# MB_RELAY.net
KiCad netlist of a schematic drawn in Altium Designer
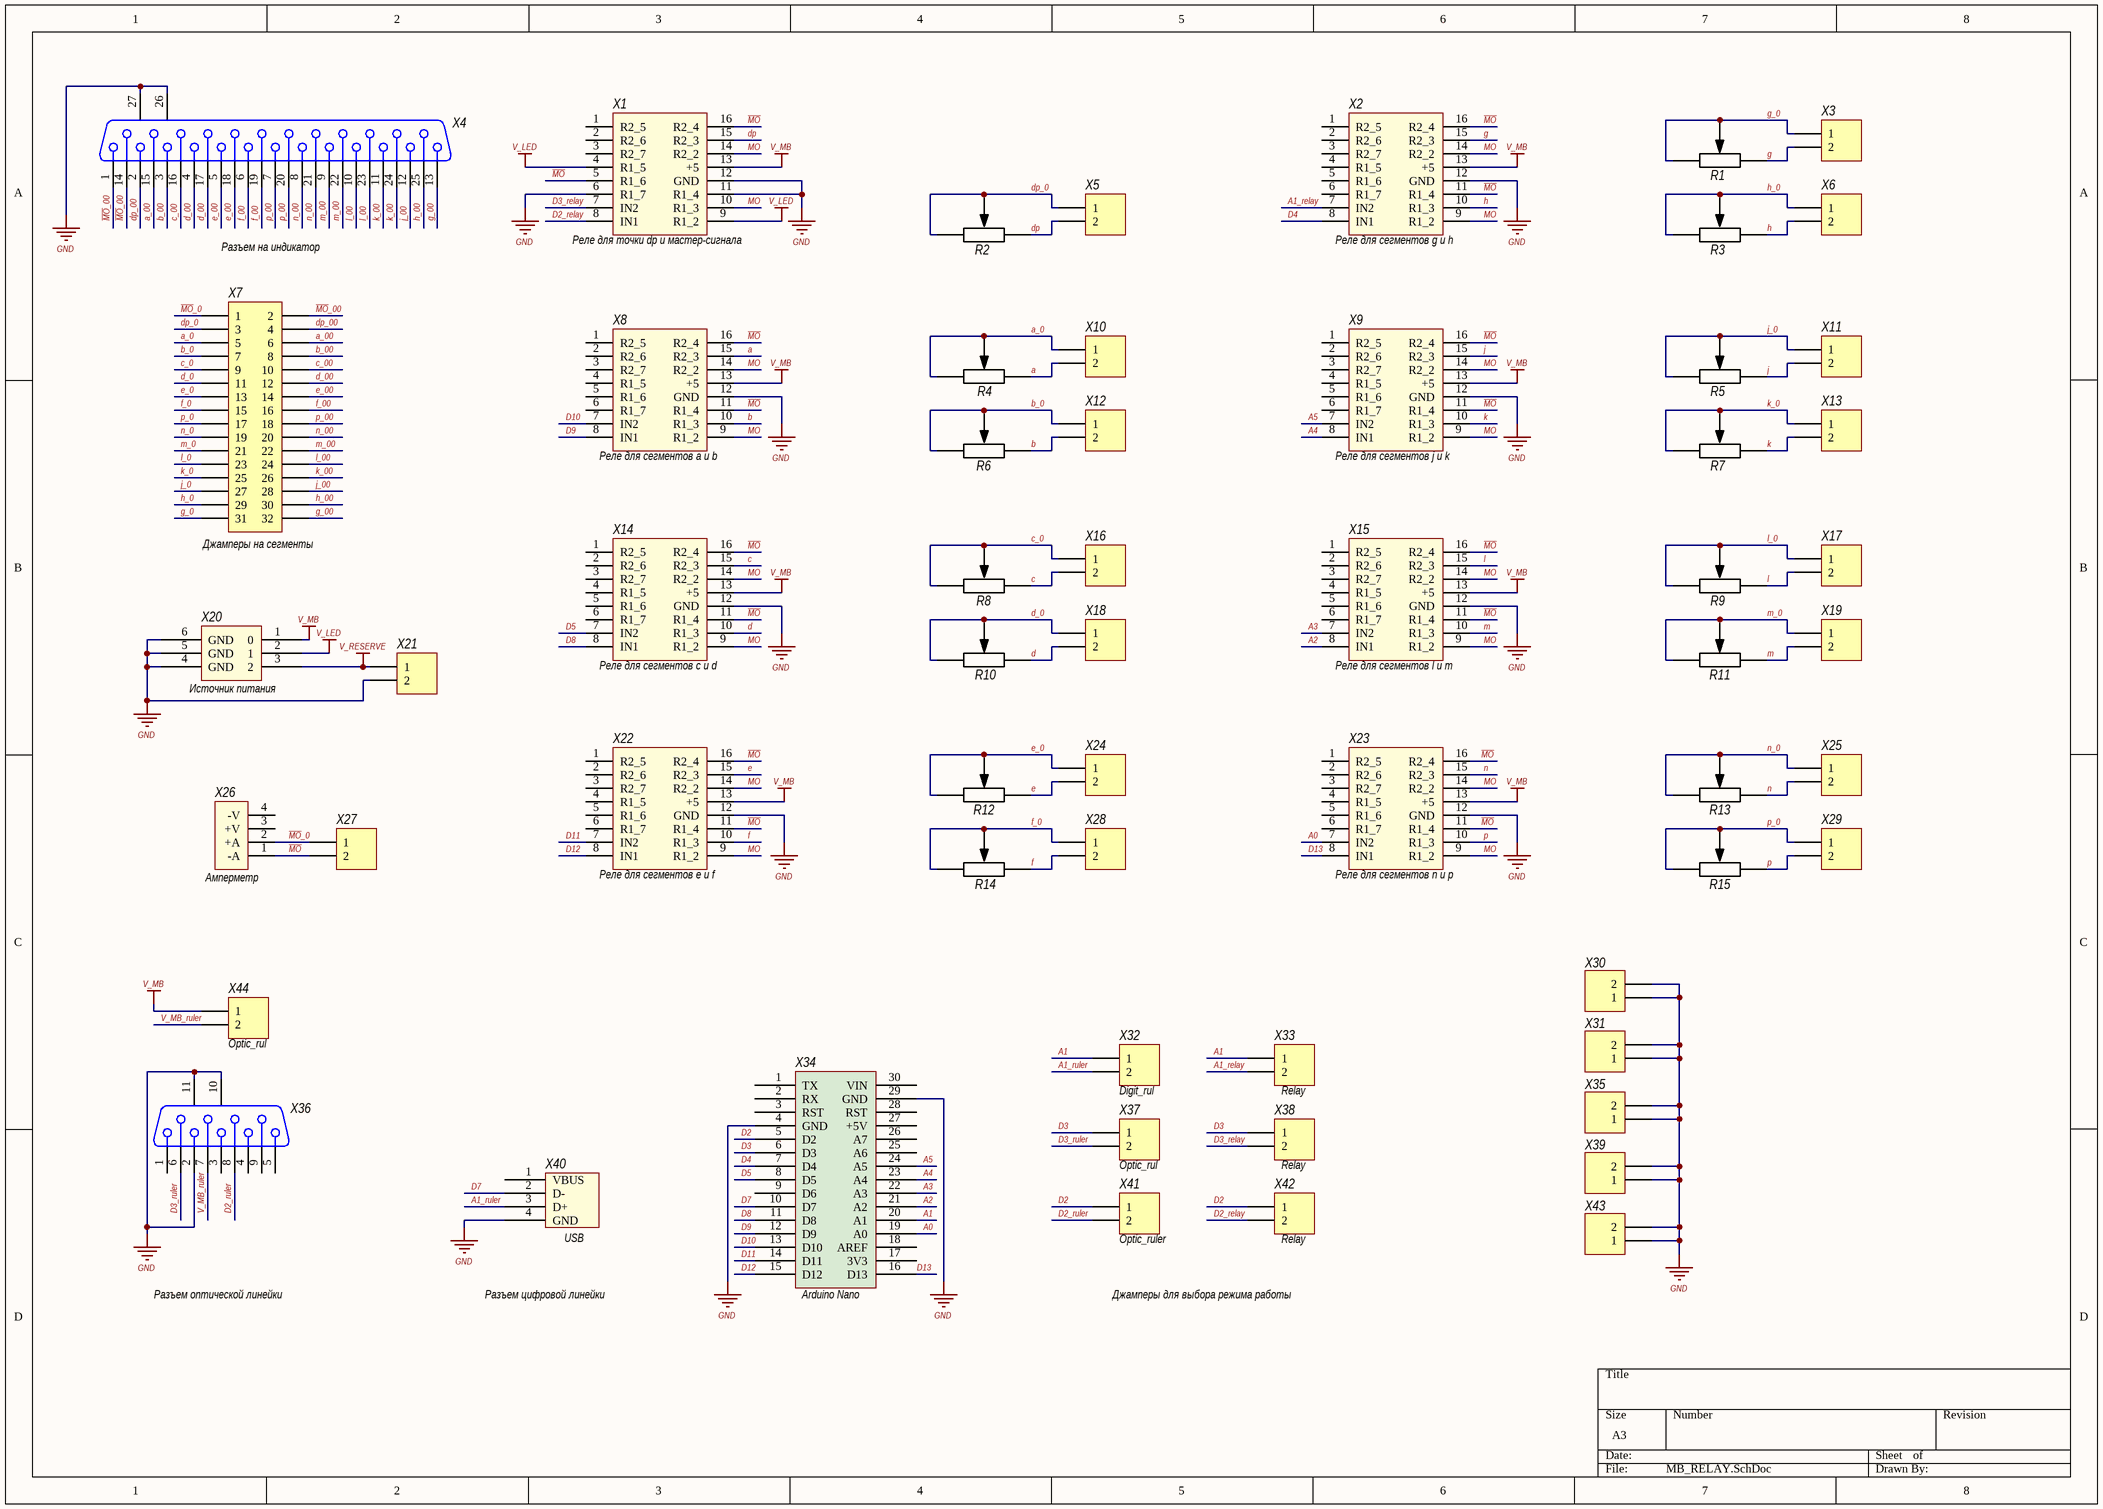
[diagram p0: MB_RELAY.SchDoc]

(export (version "E")
  (design (tool "Eeschema 10.0.6"))
  (components
    (comp (ref "R1")
      (value "RES 3266W")
      (footprint "aab_Passive:RES 3266W")
      (libsource (lib "aab_Schlib") (part "RES 3266W"))
    )
    (comp (ref "R2")
      (value "RES 3266W")
      (footprint "aab_Passive:RES 3266W")
      (libsource (lib "aab_Schlib") (part "RES 3266W"))
    )
    (comp (ref "R3")
      (value "RES 3266W")
      (footprint "aab_Passive:RES 3266W")
      (libsource (lib "aab_Schlib") (part "RES 3266W"))
    )
    (comp (ref "R4")
      (value "Переменнный резистор для")
      (footprint "aab_Passive:RES 3266W")
      (libsource (lib "aab_Schlib") (part "RES 3266W"))
    )
    (comp (ref "R5")
      (value "RES 3266W")
      (footprint "aab_Passive:RES 3266W")
      (libsource (lib "aab_Schlib") (part "RES 3266W"))
    )
    (comp (ref "R6")
      (value "RES 3266W")
      (footprint "aab_Passive:RES 3266W")
      (libsource (lib "aab_Schlib") (part "RES 3266W"))
    )
    (comp (ref "R7")
      (value "RES 3266W")
      (footprint "aab_Passive:RES 3266W")
      (libsource (lib "aab_Schlib") (part "RES 3266W"))
    )
    (comp (ref "R8")
      (value "RES 3266W")
      (footprint "aab_Passive:RES 3266W")
      (libsource (lib "aab_Schlib") (part "RES 3266W"))
    )
    (comp (ref "R9")
      (value "RES 3266W")
      (footprint "aab_Passive:RES 3266W")
      (libsource (lib "aab_Schlib") (part "RES 3266W"))
    )
    (comp (ref "R10")
      (value "RES 3266W")
      (footprint "aab_Passive:RES 3266W")
      (libsource (lib "aab_Schlib") (part "RES 3266W"))
    )
    (comp (ref "R11")
      (value "RES 3266W")
      (footprint "aab_Passive:RES 3266W")
      (libsource (lib "aab_Schlib") (part "RES 3266W"))
    )
    (comp (ref "R12")
      (value "RES 3266W")
      (footprint "aab_Passive:RES 3266W")
      (libsource (lib "aab_Schlib") (part "RES 3266W"))
    )
    (comp (ref "R13")
      (value "RES 3266W")
      (footprint "aab_Passive:RES 3266W")
      (libsource (lib "aab_Schlib") (part "RES 3266W"))
    )
    (comp (ref "R14")
      (value "RES 3266W")
      (footprint "aab_Passive:RES 3266W")
      (libsource (lib "aab_Schlib") (part "RES 3266W"))
    )
    (comp (ref "R15")
      (value "RES 3266W")
      (footprint "aab_Passive:RES 3266W")
      (libsource (lib "aab_Schlib") (part "RES 3266W"))
    )
    (comp (ref "X1")
      (value "Реле для точки dp и мастер-сигнала")
      (footprint "MEZ_RELAY")
      (libsource (lib "msp_SchLib") (part "MEZ_RELAY"))
    )
    (comp (ref "X2")
      (value "Реле для сегментов g и h")
      (footprint "MEZ_RELAY")
      (libsource (lib "msp_SchLib") (part "MEZ_RELAY"))
    )
    (comp (ref "X3")
      (value "GND")
      (footprint "HDR1X2")
      (description "Header, 2-Pin")
      (fields (field (name "PUBLISHER") "Altium Limited"))
      (libsource (lib "Miscellaneous Connectors") (part "Header 2"))
    )
    (comp (ref "X4")
      (value "D Connector 25")
      (footprint "DSUB1.385-2H25A")
      (description "Receptacle Assembly, 25 Position, Right Angle")
      (fields (field (name "PUBLISHER") "Altium Limited"))
      (libsource (lib "Miscellaneous Connectors") (part "D Connector 25"))
    )
    (comp (ref "X5")
      (value "GND")
      (footprint "HDR1X2")
      (description "Header, 2-Pin")
      (fields (field (name "PUBLISHER") "Altium Limited"))
      (libsource (lib "Miscellaneous Connectors") (part "Header 2"))
    )
    (comp (ref "X6")
      (value "GND")
      (footprint "HDR1X2")
      (description "Header, 2-Pin")
      (fields (field (name "PUBLISHER") "Altium Limited"))
      (libsource (lib "Miscellaneous Connectors") (part "Header 2"))
    )
    (comp (ref "X7")
      (value "Header 16X2")
      (footprint "HDR2X16")
      (description "Header, 16-Pin, Dual row")
      (fields (field (name "PUBLISHER") "Altium Limited"))
      (libsource (lib "Miscellaneous Connectors") (part "Header 16X2"))
    )
    (comp (ref "X8")
      (value "Реле для сегментов a и b")
      (footprint "MEZ_RELAY")
      (libsource (lib "msp_SchLib") (part "MEZ_RELAY"))
    )
    (comp (ref "X9")
      (value "Реле для сегментов j и k")
      (footprint "MEZ_RELAY")
      (libsource (lib "msp_SchLib") (part "MEZ_RELAY"))
    )
    (comp (ref "X10")
      (value "Header 2")
      (footprint "HDR1X2")
      (description "Header, 2-Pin")
      (fields (field (name "PUBLISHER") "Altium Limited"))
      (libsource (lib "Miscellaneous Connectors") (part "Header 2"))
    )
    (comp (ref "X11")
      (value "Header 2")
      (footprint "HDR1X2")
      (description "Header, 2-Pin")
      (fields (field (name "PUBLISHER") "Altium Limited"))
      (libsource (lib "Miscellaneous Connectors") (part "Header 2"))
    )
    (comp (ref "X12")
      (value "Header 2")
      (footprint "HDR1X2")
      (description "Header, 2-Pin")
      (fields (field (name "PUBLISHER") "Altium Limited"))
      (libsource (lib "Miscellaneous Connectors") (part "Header 2"))
    )
    (comp (ref "X13")
      (value "Header 2")
      (footprint "HDR1X2")
      (description "Header, 2-Pin")
      (fields (field (name "PUBLISHER") "Altium Limited"))
      (libsource (lib "Miscellaneous Connectors") (part "Header 2"))
    )
    (comp (ref "X14")
      (value "Реле для сегментов c и d")
      (footprint "MEZ_RELAY")
      (libsource (lib "msp_SchLib") (part "MEZ_RELAY"))
    )
    (comp (ref "X15")
      (value "Реле для сегментов l и m")
      (footprint "MEZ_RELAY")
      (libsource (lib "msp_SchLib") (part "MEZ_RELAY"))
    )
    (comp (ref "X16")
      (value "Header 2")
      (footprint "HDR1X2")
      (description "Header, 2-Pin")
      (fields (field (name "PUBLISHER") "Altium Limited"))
      (libsource (lib "Miscellaneous Connectors") (part "Header 2"))
    )
    (comp (ref "X17")
      (value "GND")
      (footprint "HDR1X2")
      (description "Header, 2-Pin")
      (fields (field (name "PUBLISHER") "Altium Limited"))
      (libsource (lib "Miscellaneous Connectors") (part "Header 2"))
    )
    (comp (ref "X18")
      (value "Header 2")
      (footprint "HDR1X2")
      (description "Header, 2-Pin")
      (fields (field (name "PUBLISHER") "Altium Limited"))
      (libsource (lib "Miscellaneous Connectors") (part "Header 2"))
    )
    (comp (ref "X19")
      (value "GND")
      (footprint "HDR1X2")
      (description "Header, 2-Pin")
      (fields (field (name "PUBLISHER") "Altium Limited"))
      (libsource (lib "Miscellaneous Connectors") (part "Header 2"))
    )
    (comp (ref "X20")
      (value "Источник питания")
      (footprint "vpl_Passive:POWER")
      (libsource (lib "msp_SchLib") (part "POWER"))
    )
    (comp (ref "X21")
      (value "Header 2")
      (footprint "HDR1X2")
      (description "Header, 2-Pin")
      (fields (field (name "PUBLISHER") "Altium Limited"))
      (libsource (lib "Miscellaneous Connectors") (part "Header 2"))
    )
    (comp (ref "X22")
      (value "Реле для сегментов e и f")
      (footprint "MEZ_RELAY")
      (libsource (lib "msp_SchLib") (part "MEZ_RELAY"))
    )
    (comp (ref "X23")
      (value "Реле для сегментов n и p")
      (footprint "MEZ_RELAY")
      (libsource (lib "msp_SchLib") (part "MEZ_RELAY"))
    )
    (comp (ref "X24")
      (value "GND")
      (footprint "HDR1X2")
      (description "Header, 2-Pin")
      (fields (field (name "PUBLISHER") "Altium Limited"))
      (libsource (lib "Miscellaneous Connectors") (part "Header 2"))
    )
    (comp (ref "X25")
      (value "GND")
      (footprint "HDR1X2")
      (description "Header, 2-Pin")
      (fields (field (name "PUBLISHER") "Altium Limited"))
      (libsource (lib "Miscellaneous Connectors") (part "Header 2"))
    )
    (comp (ref "X26")
      (value "Амперметр")
      (footprint "vpl_Passive:AMP_VOLTMETER")
      (libsource (lib "msp_SchLib") (part "AMP_VOLTMETR"))
    )
    (comp (ref "X27")
      (value "Header 2")
      (footprint "HDR1X2")
      (description "Header, 2-Pin")
      (fields (field (name "PUBLISHER") "Altium Limited"))
      (libsource (lib "Miscellaneous Connectors") (part "Header 2"))
    )
    (comp (ref "X28")
      (value "GND")
      (footprint "HDR1X2")
      (description "Header, 2-Pin")
      (fields (field (name "PUBLISHER") "Altium Limited"))
      (libsource (lib "Miscellaneous Connectors") (part "Header 2"))
    )
    (comp (ref "X29")
      (value "GND")
      (footprint "HDR1X2")
      (description "Header, 2-Pin")
      (fields (field (name "PUBLISHER") "Altium Limited"))
      (libsource (lib "Miscellaneous Connectors") (part "Header 2"))
    )
    (comp (ref "X30")
      (value "Header 2")
      (footprint "HDR1X2")
      (description "Header, 2-Pin")
      (fields (field (name "PUBLISHER") "Altium Limited"))
      (libsource (lib "") (part "Header 2_1"))
    )
    (comp (ref "X31")
      (value "GND")
      (footprint "HDR1X2")
      (description "Header, 2-Pin")
      (fields (field (name "PUBLISHER") "Altium Limited"))
      (libsource (lib "") (part "Header 2_1"))
    )
    (comp (ref "X32")
      (value "Digit_rul")
      (footprint "HDR1X2")
      (description "Header, 2-Pin")
      (fields (field (name "PUBLISHER") "Altium Limited"))
      (libsource (lib "Miscellaneous Connectors") (part "Header 2"))
    )
    (comp (ref "X33")
      (value "Relay")
      (footprint "HDR1X2")
      (description "Header, 2-Pin")
      (fields (field (name "PUBLISHER") "Altium Limited"))
      (libsource (lib "Miscellaneous Connectors") (part "Header 2"))
    )
    (comp (ref "X34")
      (value "Arduino Nano")
      (footprint "PCBComponent_1")
      (libsource (lib "Nano") (part "Component_1"))
    )
    (comp (ref "X35")
      (value "GND")
      (footprint "HDR1X2")
      (description "Header, 2-Pin")
      (fields (field (name "PUBLISHER") "Altium Limited"))
      (libsource (lib "") (part "Header 2_1"))
    )
    (comp (ref "X36")
      (value "D Connector 9")
      (footprint "DSUB1.385-2H9")
      (description "Receptacle Assembly, 9 Position, Right Angle")
      (fields (field (name "PUBLISHER") "Altium Limited"))
      (libsource (lib "Miscellaneous Connectors") (part "D Connector 9"))
    )
    (comp (ref "X37")
      (value "Optic_rul")
      (footprint "HDR1X2")
      (description "Header, 2-Pin")
      (fields (field (name "PUBLISHER") "Altium Limited"))
      (libsource (lib "Miscellaneous Connectors") (part "Header 2"))
    )
    (comp (ref "X38")
      (value "Relay")
      (footprint "HDR1X2")
      (description "Header, 2-Pin")
      (fields (field (name "PUBLISHER") "Altium Limited"))
      (libsource (lib "Miscellaneous Connectors") (part "Header 2"))
    )
    (comp (ref "X39")
      (value "GND")
      (footprint "HDR1X2")
      (description "Header, 2-Pin")
      (fields (field (name "PUBLISHER") "Altium Limited"))
      (libsource (lib "") (part "Header 2_1"))
    )
    (comp (ref "X40") (value "USB") (footprint "USB") (libsource (lib "msp_SchLib") (part "USB")))
    (comp (ref "X41")
      (value "Optic_ruler")
      (footprint "HDR1X2")
      (description "Header, 2-Pin")
      (fields (field (name "PUBLISHER") "Altium Limited"))
      (libsource (lib "Miscellaneous Connectors") (part "Header 2"))
    )
    (comp (ref "X42")
      (value "Relay")
      (footprint "HDR1X2")
      (description "Header, 2-Pin")
      (fields (field (name "PUBLISHER") "Altium Limited"))
      (libsource (lib "Miscellaneous Connectors") (part "Header 2"))
    )
    (comp (ref "X43")
      (value "GND")
      (footprint "HDR1X2")
      (description "Header, 2-Pin")
      (fields (field (name "PUBLISHER") "Altium Limited"))
      (libsource (lib "") (part "Header 2_1"))
    )
    (comp (ref "X44")
      (value "Optic_rul")
      (footprint "HDR1X2")
      (description "Header, 2-Pin")
      (fields (field (name "PUBLISHER") "Altium Limited"))
      (libsource (lib "Miscellaneous Connectors") (part "Header 2"))
    )
  )
  (nets
    (net (code "1") (name "/A0") (class "Default")
      (node (ref "X23") (pin "7") (pinfunction "IN2_7") (pintype "passive"))
      (node (ref "X34") (pin "19") (pinfunction "A0_19") (pintype "passive"))
    )
    (net (code "2") (name "/A1") (class "Default")
      (node (ref "X32") (pin "1") (pinfunction "1_1") (pintype "passive"))
      (node (ref "X33") (pin "1") (pinfunction "1_1") (pintype "passive"))
      (node (ref "X34") (pin "20") (pinfunction "A1_20") (pintype "passive"))
    )
    (net (code "3") (name "/A1_relay") (class "Default")
      (node (ref "X2") (pin "7") (pinfunction "IN2_7") (pintype "passive"))
      (node (ref "X33") (pin "2") (pinfunction "2_2") (pintype "passive"))
    )
    (net (code "4") (name "/A1_ruler") (class "Default")
      (node (ref "X32") (pin "2") (pinfunction "2_2") (pintype "passive"))
      (node (ref "X40") (pin "3") (pinfunction "D+_3") (pintype "passive"))
    )
    (net (code "5") (name "/A2") (class "Default")
      (node (ref "X15") (pin "8") (pinfunction "IN1_8") (pintype "passive"))
      (node (ref "X34") (pin "21") (pinfunction "A2_21") (pintype "passive"))
    )
    (net (code "6") (name "/A3") (class "Default")
      (node (ref "X15") (pin "7") (pinfunction "IN2_7") (pintype "passive"))
      (node (ref "X34") (pin "22") (pinfunction "A3_22") (pintype "passive"))
    )
    (net (code "7") (name "/A4") (class "Default")
      (node (ref "X34") (pin "23") (pinfunction "A4_23") (pintype "passive"))
      (node (ref "X9") (pin "8") (pinfunction "IN1_8") (pintype "passive"))
    )
    (net (code "8") (name "/A5") (class "Default")
      (node (ref "X34") (pin "24") (pinfunction "A5_24") (pintype "passive"))
      (node (ref "X9") (pin "7") (pinfunction "IN2_7") (pintype "passive"))
    )
    (net (code "9") (name "/D2") (class "Default")
      (node (ref "X34") (pin "5") (pinfunction "D2_5") (pintype "passive"))
      (node (ref "X41") (pin "1") (pinfunction "1_1") (pintype "passive"))
      (node (ref "X42") (pin "1") (pinfunction "1_1") (pintype "passive"))
    )
    (net (code "10") (name "/D2_relay") (class "Default")
      (node (ref "X1") (pin "8") (pinfunction "IN1_8") (pintype "passive"))
      (node (ref "X42") (pin "2") (pinfunction "2_2") (pintype "passive"))
    )
    (net (code "11") (name "/D2_ruler") (class "Default")
      (node (ref "X36") (pin "8") (pinfunction "8_8") (pintype "passive"))
      (node (ref "X41") (pin "2") (pinfunction "2_2") (pintype "passive"))
    )
    (net (code "12") (name "/D3") (class "Default")
      (node (ref "X34") (pin "6") (pinfunction "D3_6") (pintype "passive"))
      (node (ref "X37") (pin "1") (pinfunction "1_1") (pintype "passive"))
      (node (ref "X38") (pin "1") (pinfunction "1_1") (pintype "passive"))
    )
    (net (code "13") (name "/D3_relay") (class "Default")
      (node (ref "X1") (pin "7") (pinfunction "IN2_7") (pintype "passive"))
      (node (ref "X38") (pin "2") (pinfunction "2_2") (pintype "passive"))
    )
    (net (code "14") (name "/D3_ruler") (class "Default")
      (node (ref "X36") (pin "6") (pinfunction "6_6") (pintype "passive"))
      (node (ref "X37") (pin "2") (pinfunction "2_2") (pintype "passive"))
    )
    (net (code "15") (name "/D4") (class "Default")
      (node (ref "X2") (pin "8") (pinfunction "IN1_8") (pintype "passive"))
      (node (ref "X34") (pin "7") (pinfunction "D4_7") (pintype "passive"))
    )
    (net (code "16") (name "/D5") (class "Default")
      (node (ref "X14") (pin "7") (pinfunction "IN2_7") (pintype "passive"))
      (node (ref "X34") (pin "8") (pinfunction "D5_8") (pintype "passive"))
    )
    (net (code "17") (name "/D7") (class "Default")
      (node (ref "X34") (pin "10") (pinfunction "D7_10") (pintype "passive"))
      (node (ref "X40") (pin "2") (pinfunction "D-_2") (pintype "passive"))
    )
    (net (code "18") (name "/D8") (class "Default")
      (node (ref "X14") (pin "8") (pinfunction "IN1_8") (pintype "passive"))
      (node (ref "X34") (pin "11") (pinfunction "D8_11") (pintype "passive"))
    )
    (net (code "19") (name "/D9") (class "Default")
      (node (ref "X34") (pin "12") (pinfunction "D9_12") (pintype "passive"))
      (node (ref "X8") (pin "8") (pinfunction "IN1_8") (pintype "passive"))
    )
    (net (code "20") (name "/D10") (class "Default")
      (node (ref "X34") (pin "13") (pinfunction "D10_13") (pintype "passive"))
      (node (ref "X8") (pin "7") (pinfunction "IN2_7") (pintype "passive"))
    )
    (net (code "21") (name "/D11") (class "Default")
      (node (ref "X22") (pin "7") (pinfunction "IN2_7") (pintype "passive"))
      (node (ref "X34") (pin "14") (pinfunction "D11_14") (pintype "passive"))
    )
    (net (code "22") (name "/D12") (class "Default")
      (node (ref "X22") (pin "8") (pinfunction "IN1_8") (pintype "passive"))
      (node (ref "X34") (pin "15") (pinfunction "D12_15") (pintype "passive"))
    )
    (net (code "23") (name "/D13") (class "Default")
      (node (ref "X23") (pin "8") (pinfunction "IN1_8") (pintype "passive"))
      (node (ref "X34") (pin "16") (pinfunction "D13_16") (pintype "passive"))
    )
    (net (code "24") (name "/MO") (class "Default")
      (node (ref "X1") (pin "10") (pinfunction "R1_3_10") (pintype "passive"))
      (node (ref "X1") (pin "14") (pinfunction "R2_2_14") (pintype "passive"))
      (node (ref "X14") (pin "14") (pinfunction "R2_2_14") (pintype "passive"))
      (node (ref "X14") (pin "9") (pinfunction "R1_2_9") (pintype "passive"))
      (node (ref "X15") (pin "14") (pinfunction "R2_2_14") (pintype "passive"))
      (node (ref "X15") (pin "9") (pinfunction "R1_2_9") (pintype "passive"))
      (node (ref "X2") (pin "14") (pinfunction "R2_2_14") (pintype "passive"))
      (node (ref "X2") (pin "9") (pinfunction "R1_2_9") (pintype "passive"))
      (node (ref "X22") (pin "14") (pinfunction "R2_2_14") (pintype "passive"))
      (node (ref "X22") (pin "9") (pinfunction "R1_2_9") (pintype "passive"))
      (node (ref "X23") (pin "14") (pinfunction "R2_2_14") (pintype "passive"))
      (node (ref "X23") (pin "9") (pinfunction "R1_2_9") (pintype "passive"))
      (node (ref "X8") (pin "14") (pinfunction "R2_2_14") (pintype "passive"))
      (node (ref "X8") (pin "9") (pinfunction "R1_2_9") (pintype "passive"))
      (node (ref "X9") (pin "14") (pinfunction "R2_2_14") (pintype "passive"))
      (node (ref "X9") (pin "9") (pinfunction "R1_2_9") (pintype "passive"))
    )
    (net (code "25") (name "/V_MB_ruler") (class "Default")
      (node (ref "X36") (pin "7") (pinfunction "7_7") (pintype "passive"))
      (node (ref "X44") (pin "2") (pinfunction "2_2") (pintype "passive"))
    )
    (net (code "26") (name "/a") (class "Default")
      (node (ref "R4") (pin "3") (pinfunction "3_3") (pintype "passive"))
      (node (ref "X10") (pin "2") (pinfunction "2_2") (pintype "passive"))
      (node (ref "X8") (pin "15") (pinfunction "R2_3_15") (pintype "passive"))
    )
    (net (code "27") (name "/a_0") (class "Default")
      (node (ref "R4") (pin "1") (pinfunction "1_1") (pintype "passive"))
      (node (ref "R4") (pin "2") (pinfunction "2_2") (pintype "passive"))
      (node (ref "X10") (pin "1") (pinfunction "1_1") (pintype "passive"))
      (node (ref "X7") (pin "5") (pinfunction "5_5") (pintype "passive"))
    )
    (net (code "28") (name "/a_00") (class "Default")
      (node (ref "X4") (pin "15") (pinfunction "15_15") (pintype "passive"))
      (node (ref "X7") (pin "6") (pinfunction "6_6") (pintype "passive"))
    )
    (net (code "29") (name "/b") (class "Default")
      (node (ref "R6") (pin "3") (pinfunction "3_3") (pintype "passive"))
      (node (ref "X12") (pin "2") (pinfunction "2_2") (pintype "passive"))
      (node (ref "X8") (pin "10") (pinfunction "R1_3_10") (pintype "passive"))
    )
    (net (code "30") (name "/b_0") (class "Default")
      (node (ref "R6") (pin "1") (pinfunction "1_1") (pintype "passive"))
      (node (ref "R6") (pin "2") (pinfunction "2_2") (pintype "passive"))
      (node (ref "X12") (pin "1") (pinfunction "1_1") (pintype "passive"))
      (node (ref "X7") (pin "7") (pinfunction "7_7") (pintype "passive"))
    )
    (net (code "31") (name "/b_00") (class "Default")
      (node (ref "X4") (pin "3") (pinfunction "3_3") (pintype "passive"))
      (node (ref "X7") (pin "8") (pinfunction "8_8") (pintype "passive"))
    )
    (net (code "32") (name "/c") (class "Default")
      (node (ref "R8") (pin "3") (pinfunction "3_3") (pintype "passive"))
      (node (ref "X14") (pin "15") (pinfunction "R2_3_15") (pintype "passive"))
      (node (ref "X16") (pin "2") (pinfunction "2_2") (pintype "passive"))
    )
    (net (code "33") (name "/c_0") (class "Default")
      (node (ref "R8") (pin "1") (pinfunction "1_1") (pintype "passive"))
      (node (ref "R8") (pin "2") (pinfunction "2_2") (pintype "passive"))
      (node (ref "X16") (pin "1") (pinfunction "1_1") (pintype "passive"))
      (node (ref "X7") (pin "9") (pinfunction "9_9") (pintype "passive"))
    )
    (net (code "34") (name "/c_00") (class "Default")
      (node (ref "X4") (pin "16") (pinfunction "16_16") (pintype "passive"))
      (node (ref "X7") (pin "10") (pinfunction "10_10") (pintype "passive"))
    )
    (net (code "35") (name "/d") (class "Default")
      (node (ref "R10") (pin "3") (pinfunction "3_3") (pintype "passive"))
      (node (ref "X14") (pin "10") (pinfunction "R1_3_10") (pintype "passive"))
      (node (ref "X18") (pin "2") (pinfunction "2_2") (pintype "passive"))
    )
    (net (code "36") (name "/d_0") (class "Default")
      (node (ref "R10") (pin "1") (pinfunction "1_1") (pintype "passive"))
      (node (ref "R10") (pin "2") (pinfunction "2_2") (pintype "passive"))
      (node (ref "X18") (pin "1") (pinfunction "1_1") (pintype "passive"))
      (node (ref "X7") (pin "11") (pinfunction "11_11") (pintype "passive"))
    )
    (net (code "37") (name "/d_00") (class "Default")
      (node (ref "X4") (pin "17") (pinfunction "17_17") (pintype "passive"))
      (node (ref "X4") (pin "4") (pinfunction "4_4") (pintype "passive"))
      (node (ref "X7") (pin "12") (pinfunction "12_12") (pintype "passive"))
    )
    (net (code "38") (name "/dp") (class "Default")
      (node (ref "R2") (pin "3") (pinfunction "3_3") (pintype "passive"))
      (node (ref "X1") (pin "15") (pinfunction "R2_3_15") (pintype "passive"))
      (node (ref "X5") (pin "2") (pinfunction "2_2") (pintype "passive"))
    )
    (net (code "39") (name "/dp_0") (class "Default")
      (node (ref "R2") (pin "1") (pinfunction "1_1") (pintype "passive"))
      (node (ref "R2") (pin "2") (pinfunction "2_2") (pintype "passive"))
      (node (ref "X5") (pin "1") (pinfunction "1_1") (pintype "passive"))
      (node (ref "X7") (pin "3") (pinfunction "3_3") (pintype "passive"))
    )
    (net (code "40") (name "/dp_00") (class "Default")
      (node (ref "X4") (pin "2") (pinfunction "2_2") (pintype "passive"))
      (node (ref "X7") (pin "4") (pinfunction "4_4") (pintype "passive"))
    )
    (net (code "41") (name "/e") (class "Default")
      (node (ref "R12") (pin "3") (pinfunction "3_3") (pintype "passive"))
      (node (ref "X22") (pin "15") (pinfunction "R2_3_15") (pintype "passive"))
      (node (ref "X24") (pin "2") (pinfunction "2_2") (pintype "passive"))
    )
    (net (code "42") (name "/e_0") (class "Default")
      (node (ref "R12") (pin "1") (pinfunction "1_1") (pintype "passive"))
      (node (ref "R12") (pin "2") (pinfunction "2_2") (pintype "passive"))
      (node (ref "X24") (pin "1") (pinfunction "1_1") (pintype "passive"))
      (node (ref "X7") (pin "13") (pinfunction "13_13") (pintype "passive"))
    )
    (net (code "43") (name "/e_00") (class "Default")
      (node (ref "X4") (pin "18") (pinfunction "18_18") (pintype "passive"))
      (node (ref "X4") (pin "5") (pinfunction "5_5") (pintype "passive"))
      (node (ref "X7") (pin "14") (pinfunction "14_14") (pintype "passive"))
    )
    (net (code "44") (name "/f") (class "Default")
      (node (ref "R14") (pin "3") (pinfunction "3_3") (pintype "passive"))
      (node (ref "X22") (pin "10") (pinfunction "R1_3_10") (pintype "passive"))
      (node (ref "X28") (pin "2") (pinfunction "2_2") (pintype "passive"))
    )
    (net (code "45") (name "/f_0") (class "Default")
      (node (ref "R14") (pin "1") (pinfunction "1_1") (pintype "passive"))
      (node (ref "R14") (pin "2") (pinfunction "2_2") (pintype "passive"))
      (node (ref "X28") (pin "1") (pinfunction "1_1") (pintype "passive"))
      (node (ref "X7") (pin "15") (pinfunction "15_15") (pintype "passive"))
    )
    (net (code "46") (name "/f_00") (class "Default")
      (node (ref "X4") (pin "19") (pinfunction "19_19") (pintype "passive"))
      (node (ref "X4") (pin "6") (pinfunction "6_6") (pintype "passive"))
      (node (ref "X7") (pin "16") (pinfunction "16_16") (pintype "passive"))
    )
    (net (code "47") (name "/g") (class "Default")
      (node (ref "R1") (pin "3") (pinfunction "3_3") (pintype "passive"))
      (node (ref "X2") (pin "15") (pinfunction "R2_3_15") (pintype "passive"))
      (node (ref "X3") (pin "2") (pinfunction "2_2") (pintype "passive"))
    )
    (net (code "48") (name "/g_00") (class "Default")
      (node (ref "X4") (pin "13") (pinfunction "13_13") (pintype "passive"))
      (node (ref "X7") (pin "32") (pinfunction "32_32") (pintype "passive"))
    )
    (net (code "49") (name "/g_0") (class "Default")
      (node (ref "R1") (pin "1") (pinfunction "1_1") (pintype "passive"))
      (node (ref "R1") (pin "2") (pinfunction "2_2") (pintype "passive"))
      (node (ref "X3") (pin "1") (pinfunction "1_1") (pintype "passive"))
      (node (ref "X7") (pin "31") (pinfunction "31_31") (pintype "passive"))
    )
    (net (code "50") (name "/h") (class "Default")
      (node (ref "R3") (pin "3") (pinfunction "3_3") (pintype "passive"))
      (node (ref "X2") (pin "10") (pinfunction "R1_3_10") (pintype "passive"))
      (node (ref "X6") (pin "2") (pinfunction "2_2") (pintype "passive"))
    )
    (net (code "51") (name "/h_00") (class "Default")
      (node (ref "X4") (pin "25") (pinfunction "25_25") (pintype "passive"))
      (node (ref "X7") (pin "30") (pinfunction "30_30") (pintype "passive"))
    )
    (net (code "52") (name "/h_0") (class "Default")
      (node (ref "R3") (pin "1") (pinfunction "1_1") (pintype "passive"))
      (node (ref "R3") (pin "2") (pinfunction "2_2") (pintype "passive"))
      (node (ref "X6") (pin "1") (pinfunction "1_1") (pintype "passive"))
      (node (ref "X7") (pin "29") (pinfunction "29_29") (pintype "passive"))
    )
    (net (code "53") (name "/j") (class "Default")
      (node (ref "R5") (pin "3") (pinfunction "3_3") (pintype "passive"))
      (node (ref "X11") (pin "2") (pinfunction "2_2") (pintype "passive"))
      (node (ref "X9") (pin "15") (pinfunction "R2_3_15") (pintype "passive"))
    )
    (net (code "54") (name "/j_00") (class "Default")
      (node (ref "X4") (pin "12") (pinfunction "12_12") (pintype "passive"))
      (node (ref "X7") (pin "28") (pinfunction "28_28") (pintype "passive"))
    )
    (net (code "55") (name "/j_0") (class "Default")
      (node (ref "R5") (pin "1") (pinfunction "1_1") (pintype "passive"))
      (node (ref "R5") (pin "2") (pinfunction "2_2") (pintype "passive"))
      (node (ref "X11") (pin "1") (pinfunction "1_1") (pintype "passive"))
      (node (ref "X7") (pin "27") (pinfunction "27_27") (pintype "passive"))
    )
    (net (code "56") (name "/k") (class "Default")
      (node (ref "R7") (pin "3") (pinfunction "3_3") (pintype "passive"))
      (node (ref "X13") (pin "2") (pinfunction "2_2") (pintype "passive"))
      (node (ref "X9") (pin "10") (pinfunction "R1_3_10") (pintype "passive"))
    )
    (net (code "57") (name "/k_00") (class "Default")
      (node (ref "X4") (pin "11") (pinfunction "11_11") (pintype "passive"))
      (node (ref "X4") (pin "24") (pinfunction "24_24") (pintype "passive"))
      (node (ref "X7") (pin "26") (pinfunction "26_26") (pintype "passive"))
    )
    (net (code "58") (name "/k_0") (class "Default")
      (node (ref "R7") (pin "1") (pinfunction "1_1") (pintype "passive"))
      (node (ref "R7") (pin "2") (pinfunction "2_2") (pintype "passive"))
      (node (ref "X13") (pin "1") (pinfunction "1_1") (pintype "passive"))
      (node (ref "X7") (pin "25") (pinfunction "25_25") (pintype "passive"))
    )
    (net (code "59") (name "/l") (class "Default")
      (node (ref "R9") (pin "3") (pinfunction "3_3") (pintype "passive"))
      (node (ref "X15") (pin "15") (pinfunction "R2_3_15") (pintype "passive"))
      (node (ref "X17") (pin "2") (pinfunction "2_2") (pintype "passive"))
    )
    (net (code "60") (name "/l_00") (class "Default")
      (node (ref "X4") (pin "10") (pinfunction "10_10") (pintype "passive"))
      (node (ref "X4") (pin "23") (pinfunction "23_23") (pintype "passive"))
      (node (ref "X7") (pin "24") (pinfunction "24_24") (pintype "passive"))
    )
    (net (code "61") (name "/l_0") (class "Default")
      (node (ref "R9") (pin "1") (pinfunction "1_1") (pintype "passive"))
      (node (ref "R9") (pin "2") (pinfunction "2_2") (pintype "passive"))
      (node (ref "X17") (pin "1") (pinfunction "1_1") (pintype "passive"))
      (node (ref "X7") (pin "23") (pinfunction "23_23") (pintype "passive"))
    )
    (net (code "62") (name "/m") (class "Default")
      (node (ref "R11") (pin "3") (pinfunction "3_3") (pintype "passive"))
      (node (ref "X15") (pin "10") (pinfunction "R1_3_10") (pintype "passive"))
      (node (ref "X19") (pin "2") (pinfunction "2_2") (pintype "passive"))
    )
    (net (code "63") (name "/m_00") (class "Default")
      (node (ref "X4") (pin "22") (pinfunction "22_22") (pintype "passive"))
      (node (ref "X4") (pin "9") (pinfunction "9_9") (pintype "passive"))
      (node (ref "X7") (pin "22") (pinfunction "22_22") (pintype "passive"))
    )
    (net (code "64") (name "/m_0") (class "Default")
      (node (ref "R11") (pin "1") (pinfunction "1_1") (pintype "passive"))
      (node (ref "R11") (pin "2") (pinfunction "2_2") (pintype "passive"))
      (node (ref "X19") (pin "1") (pinfunction "1_1") (pintype "passive"))
      (node (ref "X7") (pin "21") (pinfunction "21_21") (pintype "passive"))
    )
    (net (code "65") (name "/n") (class "Default")
      (node (ref "R13") (pin "3") (pinfunction "3_3") (pintype "passive"))
      (node (ref "X23") (pin "15") (pinfunction "R2_3_15") (pintype "passive"))
      (node (ref "X25") (pin "2") (pinfunction "2_2") (pintype "passive"))
    )
    (net (code "66") (name "/n_0") (class "Default")
      (node (ref "R13") (pin "1") (pinfunction "1_1") (pintype "passive"))
      (node (ref "R13") (pin "2") (pinfunction "2_2") (pintype "passive"))
      (node (ref "X25") (pin "1") (pinfunction "1_1") (pintype "passive"))
      (node (ref "X7") (pin "19") (pinfunction "19_19") (pintype "passive"))
    )
    (net (code "67") (name "/n_00") (class "Default")
      (node (ref "X4") (pin "21") (pinfunction "21_21") (pintype "passive"))
      (node (ref "X4") (pin "8") (pinfunction "8_8") (pintype "passive"))
      (node (ref "X7") (pin "20") (pinfunction "20_20") (pintype "passive"))
    )
    (net (code "68") (name "/p") (class "Default")
      (node (ref "R15") (pin "3") (pinfunction "3_3") (pintype "passive"))
      (node (ref "X23") (pin "10") (pinfunction "R1_3_10") (pintype "passive"))
      (node (ref "X29") (pin "2") (pinfunction "2_2") (pintype "passive"))
    )
    (net (code "69") (name "/p_00") (class "Default")
      (node (ref "X4") (pin "20") (pinfunction "20_20") (pintype "passive"))
      (node (ref "X4") (pin "7") (pinfunction "7_7") (pintype "passive"))
      (node (ref "X7") (pin "18") (pinfunction "18_18") (pintype "passive"))
    )
    (net (code "70") (name "/p_0") (class "Default")
      (node (ref "R15") (pin "1") (pinfunction "1_1") (pintype "passive"))
      (node (ref "R15") (pin "2") (pinfunction "2_2") (pintype "passive"))
      (node (ref "X29") (pin "1") (pinfunction "1_1") (pintype "passive"))
      (node (ref "X7") (pin "17") (pinfunction "17_17") (pintype "passive"))
    )
    (net (code "71") (name "/~{MO}") (class "Default")
      (node (ref "X1") (pin "16") (pinfunction "R2_4_16") (pintype "passive"))
      (node (ref "X1") (pin "5") (pinfunction "R1_6_5") (pintype "passive"))
      (node (ref "X14") (pin "11") (pinfunction "R1_4_11") (pintype "passive"))
      (node (ref "X14") (pin "16") (pinfunction "R2_4_16") (pintype "passive"))
      (node (ref "X15") (pin "11") (pinfunction "R1_4_11") (pintype "passive"))
      (node (ref "X15") (pin "16") (pinfunction "R2_4_16") (pintype "passive"))
      (node (ref "X2") (pin "11") (pinfunction "R1_4_11") (pintype "passive"))
      (node (ref "X2") (pin "16") (pinfunction "R2_4_16") (pintype "passive"))
      (node (ref "X22") (pin "11") (pinfunction "R1_4_11") (pintype "passive"))
      (node (ref "X22") (pin "16") (pinfunction "R2_4_16") (pintype "passive"))
      (node (ref "X23") (pin "11") (pinfunction "R1_4_11") (pintype "passive"))
      (node (ref "X23") (pin "16") (pinfunction "R2_4_16") (pintype "passive"))
      (node (ref "X26") (pin "1") (pinfunction "-A_1") (pintype "passive"))
      (node (ref "X27") (pin "2") (pinfunction "2_2") (pintype "passive"))
      (node (ref "X8") (pin "11") (pinfunction "R1_4_11") (pintype "passive"))
      (node (ref "X8") (pin "16") (pinfunction "R2_4_16") (pintype "passive"))
      (node (ref "X9") (pin "11") (pinfunction "R1_4_11") (pintype "passive"))
      (node (ref "X9") (pin "16") (pinfunction "R2_4_16") (pintype "passive"))
    )
    (net (code "72") (name "/~{MO}_0") (class "Default")
      (node (ref "X26") (pin "2") (pinfunction "+A_2") (pintype "passive"))
      (node (ref "X27") (pin "1") (pinfunction "1_1") (pintype "passive"))
      (node (ref "X7") (pin "1") (pinfunction "1_1") (pintype "passive"))
    )
    (net (code "73") (name "/~{MO}_00") (class "Default")
      (node (ref "X4") (pin "1") (pinfunction "1_1") (pintype "passive"))
      (node (ref "X4") (pin "14") (pinfunction "14_14") (pintype "passive"))
      (node (ref "X7") (pin "2") (pinfunction "2_2") (pintype "passive"))
    )
    (net (code "74") (name "GND") (class "Default")
      (node (ref "X1") (pin "11") (pinfunction "R1_4_11") (pintype "passive"))
      (node (ref "X1") (pin "12") (pinfunction "GND_12") (pintype "passive"))
      (node (ref "X1") (pin "6") (pinfunction "R1_7_6") (pintype "passive"))
      (node (ref "X14") (pin "12") (pinfunction "GND_12") (pintype "passive"))
      (node (ref "X15") (pin "12") (pinfunction "GND_12") (pintype "passive"))
      (node (ref "X2") (pin "12") (pinfunction "GND_12") (pintype "passive"))
      (node (ref "X20") (pin "4") (pinfunction "GND_4") (pintype "passive"))
      (node (ref "X20") (pin "5") (pinfunction "GND_5") (pintype "passive"))
      (node (ref "X20") (pin "6") (pinfunction "GND_6") (pintype "passive"))
      (node (ref "X21") (pin "2") (pinfunction "2_2") (pintype "passive"))
      (node (ref "X22") (pin "12") (pinfunction "GND_12") (pintype "passive"))
      (node (ref "X23") (pin "12") (pinfunction "GND_12") (pintype "passive"))
      (node (ref "X30") (pin "1") (pinfunction "1_1") (pintype "passive"))
      (node (ref "X30") (pin "2") (pinfunction "2_2") (pintype "passive"))
      (node (ref "X31") (pin "1") (pinfunction "1_1") (pintype "passive"))
      (node (ref "X31") (pin "2") (pinfunction "2_2") (pintype "passive"))
      (node (ref "X34") (pin "29") (pinfunction "GND_29") (pintype "passive"))
      (node (ref "X34") (pin "4") (pinfunction "GND_4") (pintype "passive"))
      (node (ref "X35") (pin "1") (pinfunction "1_1") (pintype "passive"))
      (node (ref "X35") (pin "2") (pinfunction "2_2") (pintype "passive"))
      (node (ref "X36") (pin "10") (pinfunction "MH1_10") (pintype "passive"))
      (node (ref "X36") (pin "11") (pinfunction "MH2_11") (pintype "passive"))
      (node (ref "X36") (pin "2") (pinfunction "2_2") (pintype "passive"))
      (node (ref "X39") (pin "1") (pinfunction "1_1") (pintype "passive"))
      (node (ref "X39") (pin "2") (pinfunction "2_2") (pintype "passive"))
      (node (ref "X4") (pin "26") (pinfunction "MH1_26") (pintype "passive"))
      (node (ref "X4") (pin "27") (pinfunction "MH2_27") (pintype "passive"))
      (node (ref "X40") (pin "4") (pinfunction "GND_4") (pintype "passive"))
      (node (ref "X43") (pin "1") (pinfunction "1_1") (pintype "passive"))
      (node (ref "X43") (pin "2") (pinfunction "2_2") (pintype "passive"))
      (node (ref "X8") (pin "12") (pinfunction "GND_12") (pintype "passive"))
      (node (ref "X9") (pin "12") (pinfunction "GND_12") (pintype "passive"))
    )
    (net (code "75") (name "V_LED") (class "Default")
      (node (ref "X1") (pin "4") (pinfunction "R1_5_4") (pintype "passive"))
      (node (ref "X1") (pin "9") (pinfunction "R1_2_9") (pintype "passive"))
      (node (ref "X20") (pin "2") (pinfunction "1_2") (pintype "passive"))
    )
    (net (code "76") (name "V_MB") (class "Default")
      (node (ref "X1") (pin "13") (pinfunction "+5_13") (pintype "passive"))
      (node (ref "X14") (pin "13") (pinfunction "+5_13") (pintype "passive"))
      (node (ref "X15") (pin "13") (pinfunction "+5_13") (pintype "passive"))
      (node (ref "X2") (pin "13") (pinfunction "+5_13") (pintype "passive"))
      (node (ref "X20") (pin "1") (pinfunction "0_1") (pintype "passive"))
      (node (ref "X22") (pin "13") (pinfunction "+5_13") (pintype "passive"))
      (node (ref "X23") (pin "13") (pinfunction "+5_13") (pintype "passive"))
      (node (ref "X44") (pin "1") (pinfunction "1_1") (pintype "passive"))
      (node (ref "X8") (pin "13") (pinfunction "+5_13") (pintype "passive"))
      (node (ref "X9") (pin "13") (pinfunction "+5_13") (pintype "passive"))
    )
    (net (code "77") (name "V_RESERVE") (class "Default")
      (node (ref "X20") (pin "3") (pinfunction "2_3") (pintype "passive"))
      (node (ref "X21") (pin "1") (pinfunction "1_1") (pintype "passive"))
    )
    (net (code "78") (name "unconnected-(X1-R2_5-Pad1)") (class "Default")
      (node (ref "X1") (pin "1") (pinfunction "R2_5_1") (pintype "passive"))
    )
    (net (code "79") (name "unconnected-(X1-R2_6-Pad2)") (class "Default")
      (node (ref "X1") (pin "2") (pinfunction "R2_6_2") (pintype "passive"))
    )
    (net (code "80") (name "unconnected-(X1-R2_7-Pad3)") (class "Default")
      (node (ref "X1") (pin "3") (pinfunction "R2_7_3") (pintype "passive"))
    )
    (net (code "81") (name "unconnected-(X2-R1_5-Pad4)") (class "Default")
      (node (ref "X2") (pin "4") (pinfunction "R1_5_4") (pintype "passive"))
    )
    (net (code "82") (name "unconnected-(X2-R1_6-Pad5)") (class "Default")
      (node (ref "X2") (pin "5") (pinfunction "R1_6_5") (pintype "passive"))
    )
    (net (code "83") (name "unconnected-(X2-R1_7-Pad6)") (class "Default")
      (node (ref "X2") (pin "6") (pinfunction "R1_7_6") (pintype "passive"))
    )
    (net (code "84") (name "unconnected-(X2-R2_5-Pad1)") (class "Default")
      (node (ref "X2") (pin "1") (pinfunction "R2_5_1") (pintype "passive"))
    )
    (net (code "85") (name "unconnected-(X2-R2_6-Pad2)") (class "Default")
      (node (ref "X2") (pin "2") (pinfunction "R2_6_2") (pintype "passive"))
    )
    (net (code "86") (name "unconnected-(X2-R2_7-Pad3)") (class "Default")
      (node (ref "X2") (pin "3") (pinfunction "R2_7_3") (pintype "passive"))
    )
    (net (code "87") (name "unconnected-(X8-R1_5-Pad4)") (class "Default")
      (node (ref "X8") (pin "4") (pinfunction "R1_5_4") (pintype "passive"))
    )
    (net (code "88") (name "unconnected-(X8-R1_6-Pad5)") (class "Default")
      (node (ref "X8") (pin "5") (pinfunction "R1_6_5") (pintype "passive"))
    )
    (net (code "89") (name "unconnected-(X8-R1_7-Pad6)") (class "Default")
      (node (ref "X8") (pin "6") (pinfunction "R1_7_6") (pintype "passive"))
    )
    (net (code "90") (name "unconnected-(X8-R2_5-Pad1)") (class "Default")
      (node (ref "X8") (pin "1") (pinfunction "R2_5_1") (pintype "passive"))
    )
    (net (code "91") (name "unconnected-(X8-R2_6-Pad2)") (class "Default")
      (node (ref "X8") (pin "2") (pinfunction "R2_6_2") (pintype "passive"))
    )
    (net (code "92") (name "unconnected-(X8-R2_7-Pad3)") (class "Default")
      (node (ref "X8") (pin "3") (pinfunction "R2_7_3") (pintype "passive"))
    )
    (net (code "93") (name "unconnected-(X9-R1_5-Pad4)") (class "Default")
      (node (ref "X9") (pin "4") (pinfunction "R1_5_4") (pintype "passive"))
    )
    (net (code "94") (name "unconnected-(X9-R1_6-Pad5)") (class "Default")
      (node (ref "X9") (pin "5") (pinfunction "R1_6_5") (pintype "passive"))
    )
    (net (code "95") (name "unconnected-(X9-R1_7-Pad6)") (class "Default")
      (node (ref "X9") (pin "6") (pinfunction "R1_7_6") (pintype "passive"))
    )
    (net (code "96") (name "unconnected-(X9-R2_5-Pad1)") (class "Default")
      (node (ref "X9") (pin "1") (pinfunction "R2_5_1") (pintype "passive"))
    )
    (net (code "97") (name "unconnected-(X9-R2_6-Pad2)") (class "Default")
      (node (ref "X9") (pin "2") (pinfunction "R2_6_2") (pintype "passive"))
    )
    (net (code "98") (name "unconnected-(X9-R2_7-Pad3)") (class "Default")
      (node (ref "X9") (pin "3") (pinfunction "R2_7_3") (pintype "passive"))
    )
    (net (code "99") (name "unconnected-(X14-R1_5-Pad4)") (class "Default")
      (node (ref "X14") (pin "4") (pinfunction "R1_5_4") (pintype "passive"))
    )
    (net (code "100") (name "unconnected-(X14-R1_6-Pad5)") (class "Default")
      (node (ref "X14") (pin "5") (pinfunction "R1_6_5") (pintype "passive"))
    )
    (net (code "101") (name "unconnected-(X14-R1_7-Pad6)") (class "Default")
      (node (ref "X14") (pin "6") (pinfunction "R1_7_6") (pintype "passive"))
    )
    (net (code "102") (name "unconnected-(X14-R2_5-Pad1)") (class "Default")
      (node (ref "X14") (pin "1") (pinfunction "R2_5_1") (pintype "passive"))
    )
    (net (code "103") (name "unconnected-(X14-R2_6-Pad2)") (class "Default")
      (node (ref "X14") (pin "2") (pinfunction "R2_6_2") (pintype "passive"))
    )
    (net (code "104") (name "unconnected-(X14-R2_7-Pad3)") (class "Default")
      (node (ref "X14") (pin "3") (pinfunction "R2_7_3") (pintype "passive"))
    )
    (net (code "105") (name "unconnected-(X15-R1_5-Pad4)") (class "Default")
      (node (ref "X15") (pin "4") (pinfunction "R1_5_4") (pintype "passive"))
    )
    (net (code "106") (name "unconnected-(X15-R1_6-Pad5)") (class "Default")
      (node (ref "X15") (pin "5") (pinfunction "R1_6_5") (pintype "passive"))
    )
    (net (code "107") (name "unconnected-(X15-R1_7-Pad6)") (class "Default")
      (node (ref "X15") (pin "6") (pinfunction "R1_7_6") (pintype "passive"))
    )
    (net (code "108") (name "unconnected-(X15-R2_5-Pad1)") (class "Default")
      (node (ref "X15") (pin "1") (pinfunction "R2_5_1") (pintype "passive"))
    )
    (net (code "109") (name "unconnected-(X15-R2_6-Pad2)") (class "Default")
      (node (ref "X15") (pin "2") (pinfunction "R2_6_2") (pintype "passive"))
    )
    (net (code "110") (name "unconnected-(X15-R2_7-Pad3)") (class "Default")
      (node (ref "X15") (pin "3") (pinfunction "R2_7_3") (pintype "passive"))
    )
    (net (code "111") (name "unconnected-(X22-R1_5-Pad4)") (class "Default")
      (node (ref "X22") (pin "4") (pinfunction "R1_5_4") (pintype "passive"))
    )
    (net (code "112") (name "unconnected-(X22-R1_6-Pad5)") (class "Default")
      (node (ref "X22") (pin "5") (pinfunction "R1_6_5") (pintype "passive"))
    )
    (net (code "113") (name "unconnected-(X22-R1_7-Pad6)") (class "Default")
      (node (ref "X22") (pin "6") (pinfunction "R1_7_6") (pintype "passive"))
    )
    (net (code "114") (name "unconnected-(X22-R2_5-Pad1)") (class "Default")
      (node (ref "X22") (pin "1") (pinfunction "R2_5_1") (pintype "passive"))
    )
    (net (code "115") (name "unconnected-(X22-R2_6-Pad2)") (class "Default")
      (node (ref "X22") (pin "2") (pinfunction "R2_6_2") (pintype "passive"))
    )
    (net (code "116") (name "unconnected-(X22-R2_7-Pad3)") (class "Default")
      (node (ref "X22") (pin "3") (pinfunction "R2_7_3") (pintype "passive"))
    )
    (net (code "117") (name "unconnected-(X23-R1_5-Pad4)") (class "Default")
      (node (ref "X23") (pin "4") (pinfunction "R1_5_4") (pintype "passive"))
    )
    (net (code "118") (name "unconnected-(X23-R1_6-Pad5)") (class "Default")
      (node (ref "X23") (pin "5") (pinfunction "R1_6_5") (pintype "passive"))
    )
    (net (code "119") (name "unconnected-(X23-R1_7-Pad6)") (class "Default")
      (node (ref "X23") (pin "6") (pinfunction "R1_7_6") (pintype "passive"))
    )
    (net (code "120") (name "unconnected-(X23-R2_5-Pad1)") (class "Default")
      (node (ref "X23") (pin "1") (pinfunction "R2_5_1") (pintype "passive"))
    )
    (net (code "121") (name "unconnected-(X23-R2_6-Pad2)") (class "Default")
      (node (ref "X23") (pin "2") (pinfunction "R2_6_2") (pintype "passive"))
    )
    (net (code "122") (name "unconnected-(X23-R2_7-Pad3)") (class "Default")
      (node (ref "X23") (pin "3") (pinfunction "R2_7_3") (pintype "passive"))
    )
    (net (code "123") (name "unconnected-(X26-+V-Pad3)") (class "Default")
      (node (ref "X26") (pin "3") (pinfunction "+V_3") (pintype "passive"))
    )
    (net (code "124") (name "unconnected-(X26--V-Pad4)") (class "Default")
      (node (ref "X26") (pin "4") (pinfunction "-V_4") (pintype "passive"))
    )
    (net (code "125") (name "unconnected-(X34-+5V-Pad27)") (class "Default")
      (node (ref "X34") (pin "27") (pinfunction "+5V_27") (pintype "passive"))
    )
    (net (code "126") (name "unconnected-(X34-3V3-Pad17)") (class "Default")
      (node (ref "X34") (pin "17") (pinfunction "3V3_17") (pintype "passive"))
    )
    (net (code "127") (name "unconnected-(X34-A6-Pad25)") (class "Default")
      (node (ref "X34") (pin "25") (pinfunction "A6_25") (pintype "passive"))
    )
    (net (code "128") (name "unconnected-(X34-A7-Pad26)") (class "Default")
      (node (ref "X34") (pin "26") (pinfunction "A7_26") (pintype "passive"))
    )
    (net (code "129") (name "unconnected-(X34-AREF-Pad18)") (class "Default")
      (node (ref "X34") (pin "18") (pinfunction "AREF_18") (pintype "passive"))
    )
    (net (code "130") (name "unconnected-(X34-D6-Pad9)") (class "Default")
      (node (ref "X34") (pin "9") (pinfunction "D6_9") (pintype "passive"))
    )
    (net (code "131") (name "unconnected-(X34-RST-Pad3)") (class "Default")
      (node (ref "X34") (pin "3") (pinfunction "RST_3") (pintype "passive"))
    )
    (net (code "132") (name "unconnected-(X34-RST-Pad28)") (class "Default")
      (node (ref "X34") (pin "28") (pinfunction "RST_28") (pintype "passive"))
    )
    (net (code "133") (name "unconnected-(X34-RX-Pad2)") (class "Default")
      (node (ref "X34") (pin "2") (pinfunction "RX_2") (pintype "passive"))
    )
    (net (code "134") (name "unconnected-(X34-TX-Pad1)") (class "Default")
      (node (ref "X34") (pin "1") (pinfunction "TX_1") (pintype "passive"))
    )
    (net (code "135") (name "unconnected-(X34-VIN-Pad30)") (class "Default")
      (node (ref "X34") (pin "30") (pinfunction "VIN_30") (pintype "passive"))
    )
    (net (code "136") (name "unconnected-(X36-Pad1)") (class "Default")
      (node (ref "X36") (pin "1") (pinfunction "1_1") (pintype "passive"))
    )
    (net (code "137") (name "unconnected-(X36-Pad3)") (class "Default")
      (node (ref "X36") (pin "3") (pinfunction "3_3") (pintype "passive"))
    )
    (net (code "138") (name "unconnected-(X36-Pad4)") (class "Default")
      (node (ref "X36") (pin "4") (pinfunction "4_4") (pintype "passive"))
    )
    (net (code "139") (name "unconnected-(X36-Pad5)") (class "Default")
      (node (ref "X36") (pin "5") (pinfunction "5_5") (pintype "passive"))
    )
    (net (code "140") (name "unconnected-(X36-Pad9)") (class "Default")
      (node (ref "X36") (pin "9") (pinfunction "9_9") (pintype "passive"))
    )
    (net (code "141") (name "unconnected-(X40-VBUS-Pad1)") (class "Default")
      (node (ref "X40") (pin "1") (pinfunction "VBUS_1") (pintype "passive"))
    )
  )
)
